# design.net
KiCad netlist of a schematic drawn in Altium Designer
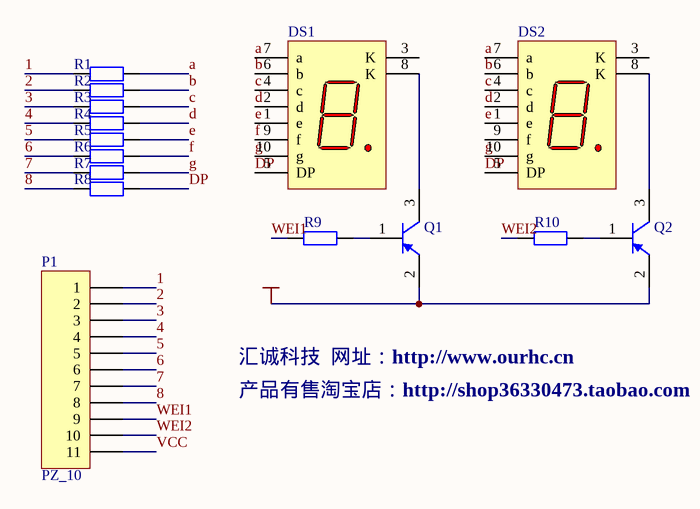
[diagram p0: 两位数码管显示模块.SCHDOC]

(export (version "E")
  (design (tool "Eeschema 10.0.6"))
  (components
    (comp (ref "DS1")
      (value "DLSMG_B")
      (footprint "LED-BSR")
      (description "独立共阳数码管")
      (fields (field (name "PUBLISHER") "Altium Limited"))
      (libsource (lib "zxcourhc") (part "DLSMG_B"))
    )
    (comp (ref "DS2")
      (value "DLSMG_B")
      (footprint "LED-BSR")
      (description "独立共阳数码管")
      (fields (field (name "PUBLISHER") "Altium Limited"))
      (libsource (lib "zxcourhc") (part "DLSMG_B"))
    )
    (comp (ref "P1")
      (value "PZ_10")
      (footprint "PCB1:HDR-10")
      (description "排针——10")
      (fields (field (name "PUBLISHER") "Altium Limited"))
      (libsource (lib "数码管") (part "PZ_10"))
    )
    (comp (ref "Q1")
      (value "TPSJG_PNP")
      (footprint "zxcourhc:SO-G3")
      (description "贴片三极管——PNP")
      (fields (field (name "PUBLISHER") "Altium Limited"))
      (libsource (lib "") (part "TPSJG_PNP_1"))
    )
    (comp (ref "Q2")
      (value "TPSJG_PNP")
      (footprint "zxcourhc:SO-G3")
      (description "贴片三极管——PNP")
      (fields (field (name "PUBLISHER") "Altium Limited"))
      (libsource (lib "zxcourhc") (part "TPSJG_PNP"))
    )
    (comp (ref "R1")
      (value "Res")
      (footprint "zxcourhc:0805")
      (description "电阻")
      (fields (field (name "PUBLISHER") "Altium Limited"))
      (libsource (lib "zxcourhc") (part "Res"))
    )
    (comp (ref "R2")
      (value "Res")
      (footprint "zxcourhc:0805")
      (description "电阻")
      (fields (field (name "PUBLISHER") "Altium Limited"))
      (libsource (lib "zxcourhc") (part "Res"))
    )
    (comp (ref "R3")
      (value "Res")
      (footprint "zxcourhc:0805")
      (description "电阻")
      (fields (field (name "PUBLISHER") "Altium Limited"))
      (libsource (lib "zxcourhc") (part "Res"))
    )
    (comp (ref "R4")
      (value "Res")
      (footprint "zxcourhc:0805")
      (description "电阻")
      (fields (field (name "PUBLISHER") "Altium Limited"))
      (libsource (lib "zxcourhc") (part "Res"))
    )
    (comp (ref "R5")
      (value "Res")
      (footprint "zxcourhc:0805")
      (description "电阻")
      (fields (field (name "PUBLISHER") "Altium Limited"))
      (libsource (lib "zxcourhc") (part "Res"))
    )
    (comp (ref "R6")
      (value "Res")
      (footprint "zxcourhc:0805")
      (description "电阻")
      (fields (field (name "PUBLISHER") "Altium Limited"))
      (libsource (lib "zxcourhc") (part "Res"))
    )
    (comp (ref "R7")
      (value "Res")
      (footprint "zxcourhc:0805")
      (description "电阻")
      (fields (field (name "PUBLISHER") "Altium Limited"))
      (libsource (lib "zxcourhc") (part "Res"))
    )
    (comp (ref "R8")
      (value "Res")
      (footprint "zxcourhc:0805")
      (description "电阻")
      (fields (field (name "PUBLISHER") "Altium Limited"))
      (libsource (lib "zxcourhc") (part "Res"))
    )
    (comp (ref "R9")
      (value "Res")
      (footprint "zxcourhc:0805")
      (description "电阻")
      (fields (field (name "PUBLISHER") "Altium Limited"))
      (libsource (lib "zxcourhc") (part "Res"))
    )
    (comp (ref "R10")
      (value "Res")
      (footprint "zxcourhc:0805")
      (description "电阻")
      (fields (field (name "PUBLISHER") "Altium Limited"))
      (libsource (lib "zxcourhc") (part "Res"))
    )
  )
  (nets
    (net (code "1") (name "/1") (class "Default")
      (node (ref "P1") (pin "1") (pinfunction "1_1") (pintype "passive"))
      (node (ref "R1") (pin "1") (pinfunction "1_1") (pintype "passive"))
    )
    (net (code "2") (name "/2") (class "Default")
      (node (ref "P1") (pin "2") (pinfunction "2_2") (pintype "passive"))
      (node (ref "R2") (pin "1") (pinfunction "1_1") (pintype "passive"))
    )
    (net (code "3") (name "/3") (class "Default")
      (node (ref "P1") (pin "3") (pinfunction "3_3") (pintype "passive"))
      (node (ref "R3") (pin "1") (pinfunction "1_1") (pintype "passive"))
    )
    (net (code "4") (name "/4") (class "Default")
      (node (ref "P1") (pin "4") (pinfunction "4_4") (pintype "passive"))
      (node (ref "R4") (pin "1") (pinfunction "1_1") (pintype "passive"))
    )
    (net (code "5") (name "/5") (class "Default")
      (node (ref "P1") (pin "5") (pinfunction "5_5") (pintype "passive"))
      (node (ref "R5") (pin "1") (pinfunction "1_1") (pintype "passive"))
    )
    (net (code "6") (name "/6") (class "Default")
      (node (ref "P1") (pin "6") (pinfunction "6_6") (pintype "passive"))
      (node (ref "R6") (pin "1") (pinfunction "1_1") (pintype "passive"))
    )
    (net (code "7") (name "/7") (class "Default")
      (node (ref "P1") (pin "7") (pinfunction "7_7") (pintype "passive"))
      (node (ref "R7") (pin "1") (pinfunction "1_1") (pintype "passive"))
    )
    (net (code "8") (name "/8") (class "Default")
      (node (ref "P1") (pin "8") (pinfunction "8_8") (pintype "passive"))
      (node (ref "R8") (pin "1") (pinfunction "1_1") (pintype "passive"))
    )
    (net (code "9") (name "/DP") (class "Default")
      (node (ref "DS1") (pin "5") (pinfunction "DP_5") (pintype "passive"))
      (node (ref "DS2") (pin "5") (pinfunction "DP_5") (pintype "passive"))
      (node (ref "R8") (pin "2") (pinfunction "2_2") (pintype "passive"))
    )
    (net (code "10") (name "/WEI1") (class "Default")
      (node (ref "P1") (pin "9") (pinfunction "9_9") (pintype "passive"))
      (node (ref "R9") (pin "1") (pinfunction "1_1") (pintype "passive"))
    )
    (net (code "11") (name "/WEI2") (class "Default")
      (node (ref "P1") (pin "10") (pinfunction "10_10") (pintype "passive"))
      (node (ref "R10") (pin "1") (pinfunction "1_1") (pintype "passive"))
    )
    (net (code "12") (name "/a") (class "Default")
      (node (ref "DS1") (pin "7") (pinfunction "a_7") (pintype "passive"))
      (node (ref "DS2") (pin "7") (pinfunction "a_7") (pintype "passive"))
      (node (ref "R1") (pin "2") (pinfunction "2_2") (pintype "passive"))
    )
    (net (code "13") (name "/b") (class "Default")
      (node (ref "DS1") (pin "6") (pinfunction "b_6") (pintype "passive"))
      (node (ref "DS2") (pin "6") (pinfunction "b_6") (pintype "passive"))
      (node (ref "R2") (pin "2") (pinfunction "2_2") (pintype "passive"))
    )
    (net (code "14") (name "/c") (class "Default")
      (node (ref "DS1") (pin "4") (pinfunction "c_4") (pintype "passive"))
      (node (ref "DS2") (pin "4") (pinfunction "c_4") (pintype "passive"))
      (node (ref "R3") (pin "2") (pinfunction "2_2") (pintype "passive"))
    )
    (net (code "15") (name "/d") (class "Default")
      (node (ref "DS1") (pin "2") (pinfunction "d_2") (pintype "passive"))
      (node (ref "DS2") (pin "2") (pinfunction "d_2") (pintype "passive"))
      (node (ref "R4") (pin "2") (pinfunction "2_2") (pintype "passive"))
    )
    (net (code "16") (name "/e") (class "Default")
      (node (ref "DS1") (pin "1") (pinfunction "e_1") (pintype "passive"))
      (node (ref "DS2") (pin "1") (pinfunction "e_1") (pintype "passive"))
      (node (ref "R5") (pin "2") (pinfunction "2_2") (pintype "passive"))
    )
    (net (code "17") (name "/f") (class "Default")
      (node (ref "DS1") (pin "9") (pinfunction "f_9") (pintype "passive"))
      (node (ref "R6") (pin "2") (pinfunction "2_2") (pintype "passive"))
    )
    (net (code "18") (name "/g") (class "Default")
      (node (ref "DS1") (pin "10") (pinfunction "g_10") (pintype "passive"))
      (node (ref "DS2") (pin "10") (pinfunction "g_10") (pintype "passive"))
      (node (ref "R7") (pin "2") (pinfunction "2_2") (pintype "passive"))
    )
    (net (code "19") (name "Net-(Q1-B)") (class "Default")
      (node (ref "Q1") (pin "1") (pinfunction "B_1") (pintype "passive"))
      (node (ref "R9") (pin "2") (pinfunction "2_2") (pintype "passive"))
    )
    (net (code "20") (name "Net-(Q1-C)") (class "Default")
      (node (ref "DS1") (pin "8") (pinfunction "K_8") (pintype "passive"))
      (node (ref "Q1") (pin "3") (pinfunction "C_3") (pintype "passive"))
    )
    (net (code "21") (name "Net-(Q2-B)") (class "Default")
      (node (ref "Q2") (pin "1") (pinfunction "B_1") (pintype "passive"))
      (node (ref "R10") (pin "2") (pinfunction "2_2") (pintype "passive"))
    )
    (net (code "22") (name "Net-(Q2-C)") (class "Default")
      (node (ref "DS2") (pin "8") (pinfunction "K_8") (pintype "passive"))
      (node (ref "Q2") (pin "3") (pinfunction "C_3") (pintype "passive"))
    )
    (net (code "23") (name "VCC") (class "Default")
      (node (ref "P1") (pin "11") (pinfunction "11_11") (pintype "passive"))
      (node (ref "Q1") (pin "2") (pinfunction "E_2") (pintype "passive"))
      (node (ref "Q2") (pin "2") (pinfunction "E_2") (pintype "passive"))
    )
    (net (code "24") (name "unconnected-(DS1-K-Pad3)") (class "Default")
      (node (ref "DS1") (pin "3") (pinfunction "K_3") (pintype "passive"))
    )
    (net (code "25") (name "unconnected-(DS2-K-Pad3)") (class "Default")
      (node (ref "DS2") (pin "3") (pinfunction "K_3") (pintype "passive"))
    )
    (net (code "26") (name "unconnected-(DS2-f-Pad9)") (class "Default")
      (node (ref "DS2") (pin "9") (pinfunction "f_9") (pintype "passive"))
    )
  )
)
